# tl.net
KiCad netlist of a schematic drawn in Altium Designer
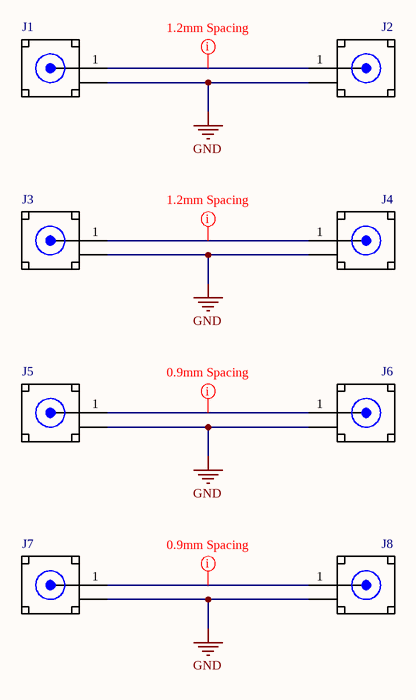
[diagram p0: tl.SchDoc]

(export (version "E")
  (design (tool "Eeschema 10.0.6"))
  (components
    (comp (ref "J1")
      (value "SMA-J-P-H-ST-EM1")
      (footprint "SAMTEC SMA-J-P-H-ST-EM1")
      (description "CONN SMA JACK STR 50OHM EDGE MNT")
      (fields (field (name "MANUFACTURER") "Samtec Inc."))
      (libsource (lib "Generic Altium Database") (part "SAMTEC SMA-J-P-H-ST-EM1"))
    )
    (comp (ref "J2")
      (value "SMA-J-P-H-ST-EM1")
      (footprint "SAMTEC SMA-J-P-H-ST-EM1")
      (description "CONN SMA JACK STR 50OHM EDGE MNT")
      (fields (field (name "MANUFACTURER") "Samtec Inc."))
      (libsource (lib "Generic Altium Database") (part "SAMTEC SMA-J-P-H-ST-EM1"))
    )
    (comp (ref "J3")
      (value "SMA-J-P-H-ST-EM1")
      (footprint "SAMTEC SMA-J-P-H-ST-EM1")
      (description "CONN SMA JACK STR 50OHM EDGE MNT")
      (fields (field (name "MANUFACTURER") "Samtec Inc."))
      (libsource (lib "Generic Altium Database") (part "SAMTEC SMA-J-P-H-ST-EM1"))
    )
    (comp (ref "J4")
      (value "SMA-J-P-H-ST-EM1")
      (footprint "SAMTEC SMA-J-P-H-ST-EM1")
      (description "CONN SMA JACK STR 50OHM EDGE MNT")
      (fields (field (name "MANUFACTURER") "Samtec Inc."))
      (libsource (lib "Generic Altium Database") (part "SAMTEC SMA-J-P-H-ST-EM1"))
    )
    (comp (ref "J5")
      (value "SMA-J-P-H-ST-EM1")
      (footprint "SAMTEC SMA-J-P-H-ST-EM1")
      (description "CONN SMA JACK STR 50OHM EDGE MNT")
      (fields (field (name "MANUFACTURER") "Samtec Inc."))
      (libsource (lib "Generic Altium Database") (part "SAMTEC SMA-J-P-H-ST-EM1"))
    )
    (comp (ref "J6")
      (value "SMA-J-P-H-ST-EM1")
      (footprint "SAMTEC SMA-J-P-H-ST-EM1")
      (description "CONN SMA JACK STR 50OHM EDGE MNT")
      (fields (field (name "MANUFACTURER") "Samtec Inc."))
      (libsource (lib "Generic Altium Database") (part "SAMTEC SMA-J-P-H-ST-EM1"))
    )
    (comp (ref "J7")
      (value "SMA-J-P-H-ST-EM1")
      (footprint "SAMTEC SMA-J-P-H-ST-EM1")
      (description "CONN SMA JACK STR 50OHM EDGE MNT")
      (fields (field (name "MANUFACTURER") "Samtec Inc."))
      (libsource (lib "Generic Altium Database") (part "SAMTEC SMA-J-P-H-ST-EM1"))
    )
    (comp (ref "J8")
      (value "SMA-J-P-H-ST-EM1")
      (footprint "SAMTEC SMA-J-P-H-ST-EM1")
      (description "CONN SMA JACK STR 50OHM EDGE MNT")
      (fields (field (name "MANUFACTURER") "Samtec Inc."))
      (libsource (lib "Generic Altium Database") (part "SAMTEC SMA-J-P-H-ST-EM1"))
    )
  )
  (nets
    (net (code "1") (name "GND") (class "Default")
      (node (ref "J1") (pin "2") (pinfunction "GND_2") (pintype "power_in"))
      (node (ref "J2") (pin "2") (pinfunction "GND_2") (pintype "power_in"))
      (node (ref "J3") (pin "2") (pinfunction "GND_2") (pintype "power_in"))
      (node (ref "J4") (pin "2") (pinfunction "GND_2") (pintype "power_in"))
      (node (ref "J5") (pin "2") (pinfunction "GND_2") (pintype "power_in"))
      (node (ref "J6") (pin "2") (pinfunction "GND_2") (pintype "power_in"))
      (node (ref "J7") (pin "2") (pinfunction "GND_2") (pintype "power_in"))
      (node (ref "J8") (pin "2") (pinfunction "GND_2") (pintype "power_in"))
    )
    (net (code "2") (name "Net-(J1-SIGNAL)") (class "Default")
      (node (ref "J1") (pin "1") (pinfunction "SIGNAL_1") (pintype "passive"))
      (node (ref "J2") (pin "1") (pinfunction "SIGNAL_1") (pintype "passive"))
    )
    (net (code "3") (name "Net-(J3-SIGNAL)") (class "Default")
      (node (ref "J3") (pin "1") (pinfunction "SIGNAL_1") (pintype "passive"))
      (node (ref "J4") (pin "1") (pinfunction "SIGNAL_1") (pintype "passive"))
    )
    (net (code "4") (name "Net-(J5-SIGNAL)") (class "Default")
      (node (ref "J5") (pin "1") (pinfunction "SIGNAL_1") (pintype "passive"))
      (node (ref "J6") (pin "1") (pinfunction "SIGNAL_1") (pintype "passive"))
    )
    (net (code "5") (name "Net-(J7-SIGNAL)") (class "Default")
      (node (ref "J7") (pin "1") (pinfunction "SIGNAL_1") (pintype "passive"))
      (node (ref "J8") (pin "1") (pinfunction "SIGNAL_1") (pintype "passive"))
    )
  )
)
